# amp.net
KiCad netlist of a schematic drawn in EAGLE
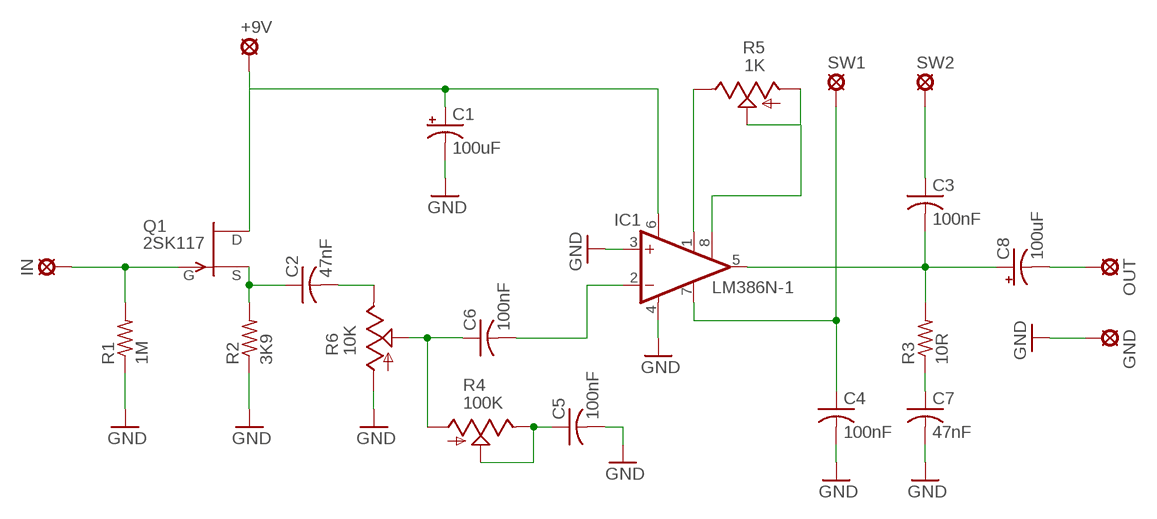
[diagram p0: schematic, sheet 1]

(export (version "E")
  (design (tool "Eeschema 10.0.6"))
  (components
    (comp (ref "+9V")
      (value "MCS10B")
      (footprint "eagle-import:MCS10B")
      (libsource (lib "eagle-import") (part "MCS10B"))
    )
    (comp (ref "C1")
      (value "100uF")
      (footprint "eagle-import:TT2D5")
      (libsource (lib "eagle-import") (part "CPOL-USTT2D5"))
    )
    (comp (ref "C2")
      (value "47nF")
      (footprint "eagle-import:C050-025X075")
      (libsource (lib "eagle-import") (part "C-US050-025X075"))
    )
    (comp (ref "C3")
      (value "100nF")
      (footprint "eagle-import:C050-025X075")
      (libsource (lib "eagle-import") (part "C-US050-025X075"))
    )
    (comp (ref "C4")
      (value "100nF")
      (footprint "eagle-import:C050-025X075")
      (libsource (lib "eagle-import") (part "C-US050-025X075"))
    )
    (comp (ref "C5")
      (value "100nF")
      (footprint "eagle-import:C050-025X075")
      (libsource (lib "eagle-import") (part "C-US050-025X075"))
    )
    (comp (ref "C6")
      (value "100nF")
      (footprint "eagle-import:C050-025X075")
      (libsource (lib "eagle-import") (part "C-US050-025X075"))
    )
    (comp (ref "C7")
      (value "47nF")
      (footprint "eagle-import:C050-025X075")
      (libsource (lib "eagle-import") (part "C-US050-025X075"))
    )
    (comp (ref "C8")
      (value "100uF")
      (footprint "eagle-import:TT2D5")
      (libsource (lib "eagle-import") (part "CPOL-USTT2D5"))
    )
    (comp (ref "GND")
      (value "MCS10B")
      (footprint "eagle-import:MCS10B")
      (libsource (lib "eagle-import") (part "MCS10B"))
    )
    (comp (ref "IC1")
      (value "LM386N-1")
      (footprint "eagle-import:DIL08")
      (libsource (lib "eagle-import") (part "LM386?-N1"))
    )
    (comp (ref "IN")
      (value "MCS10B")
      (footprint "eagle-import:MCS10B")
      (libsource (lib "eagle-import") (part "MCS10B"))
    )
    (comp (ref "OUT")
      (value "MCS10B")
      (footprint "eagle-import:MCS10B")
      (libsource (lib "eagle-import") (part "MCS10B"))
    )
    (comp (ref "Q1")
      (value "2SK117")
      (footprint "eagle-import:TO-92")
      (libsource (lib "eagle-import") (part "2SK117"))
    )
    (comp (ref "R1")
      (value "1M")
      (footprint "eagle-import:0207_7")
      (libsource (lib "eagle-import") (part "R-US_0207/7"))
    )
    (comp (ref "R2")
      (value "3K9")
      (footprint "eagle-import:0207_7")
      (libsource (lib "eagle-import") (part "R-US_0207/7"))
    )
    (comp (ref "R3")
      (value "10R")
      (footprint "eagle-import:0207_7")
      (libsource (lib "eagle-import") (part "R-US_0207/7"))
    )
    (comp (ref "R4")
      (value "100K")
      (footprint "eagle-import:B64Y")
      (libsource (lib "eagle-import") (part "TRIM_US-B64Y"))
    )
    (comp (ref "R5")
      (value "1K")
      (footprint "eagle-import:B64Y")
      (libsource (lib "eagle-import") (part "TRIM_US-B64Y"))
    )
    (comp (ref "R6")
      (value "10K")
      (footprint "eagle-import:B64Y")
      (libsource (lib "eagle-import") (part "TRIM_US-B64Y"))
    )
    (comp (ref "SW1")
      (value "MCS10B")
      (footprint "eagle-import:MCS10B")
      (libsource (lib "eagle-import") (part "MCS10B"))
    )
    (comp (ref "SW2")
      (value "MCS10B")
      (footprint "eagle-import:MCS10B")
      (libsource (lib "eagle-import") (part "MCS10B"))
    )
  )
  (nets
    (net (code "1") (name "GND") (class "Default")
      (node (ref "C1") (pin "-") (pinfunction "-_-") (pintype "passive"))
      (node (ref "C4") (pin "2") (pinfunction "2_2") (pintype "passive"))
      (node (ref "C5") (pin "2") (pinfunction "2_2") (pintype "passive"))
      (node (ref "C7") (pin "2") (pinfunction "2_2") (pintype "passive"))
      (node (ref "GND") (pin "MP") (pinfunction "MP_MP") (pintype "passive"))
      (node (ref "IC1") (pin "3") (pinfunction "+IN_3") (pintype "input"))
      (node (ref "IC1") (pin "4") (pinfunction "GND_4") (pintype "power_in"))
      (node (ref "R1") (pin "1") (pinfunction "1_1") (pintype "passive"))
      (node (ref "R2") (pin "1") (pinfunction "1_1") (pintype "passive"))
      (node (ref "R6") (pin "A") (pinfunction "A_A") (pintype "passive"))
    )
    (net (code "2") (name "Net-(C2-Pad2)") (class "Default")
      (node (ref "C2") (pin "2") (pinfunction "2_2") (pintype "passive"))
      (node (ref "R6") (pin "E") (pinfunction "E_E") (pintype "passive"))
    )
    (net (code "3") (name "Net-(C3-Pad1)") (class "Default")
      (node (ref "C3") (pin "1") (pinfunction "1_1") (pintype "passive"))
      (node (ref "SW2") (pin "MP") (pinfunction "MP_MP") (pintype "passive"))
    )
    (net (code "4") (name "Net-(C5-Pad1)") (class "Default")
      (node (ref "C5") (pin "1") (pinfunction "1_1") (pintype "passive"))
      (node (ref "R4") (pin "E") (pinfunction "E_E") (pintype "passive"))
      (node (ref "R4") (pin "S") (pinfunction "S_S") (pintype "passive"))
    )
    (net (code "5") (name "Net-(C6-Pad1)") (class "Default")
      (node (ref "C6") (pin "1") (pinfunction "1_1") (pintype "passive"))
      (node (ref "R4") (pin "A") (pinfunction "A_A") (pintype "passive"))
      (node (ref "R6") (pin "S") (pinfunction "S_S") (pintype "passive"))
    )
    (net (code "6") (name "Net-(C7-Pad1)") (class "Default")
      (node (ref "C7") (pin "1") (pinfunction "1_1") (pintype "passive"))
      (node (ref "R3") (pin "1") (pinfunction "1_1") (pintype "passive"))
    )
    (net (code "7") (name "Net-(C8-Pad-)") (class "Default")
      (node (ref "C8") (pin "-") (pinfunction "-_-") (pintype "passive"))
      (node (ref "OUT") (pin "MP") (pinfunction "MP_MP") (pintype "passive"))
    )
    (net (code "8") (name "Net-(IC1--IN)") (class "Default")
      (node (ref "C6") (pin "2") (pinfunction "2_2") (pintype "passive"))
      (node (ref "IC1") (pin "2") (pinfunction "-IN_2") (pintype "input"))
    )
    (net (code "9") (name "Net-(IC1-BYPASS)") (class "Default")
      (node (ref "C4") (pin "1") (pinfunction "1_1") (pintype "passive"))
      (node (ref "IC1") (pin "7") (pinfunction "BYPASS_7") (pintype "passive"))
      (node (ref "SW1") (pin "MP") (pinfunction "MP_MP") (pintype "passive"))
    )
    (net (code "10") (name "Net-(IC1-GAIN-Pad1)") (class "Default")
      (node (ref "IC1") (pin "1") (pinfunction "GAIN_1") (pintype "passive"))
      (node (ref "R5") (pin "E") (pinfunction "E_E") (pintype "passive"))
    )
    (net (code "11") (name "Net-(IC1-GAIN-Pad8)") (class "Default")
      (node (ref "IC1") (pin "8") (pinfunction "GAIN_8") (pintype "passive"))
      (node (ref "R5") (pin "A") (pinfunction "A_A") (pintype "passive"))
      (node (ref "R5") (pin "S") (pinfunction "S_S") (pintype "passive"))
    )
    (net (code "12") (name "Net-(IC1-OUT)") (class "Default")
      (node (ref "C3") (pin "2") (pinfunction "2_2") (pintype "passive"))
      (node (ref "C8") (pin "+") (pinfunction "+_+") (pintype "passive"))
      (node (ref "IC1") (pin "5") (pinfunction "OUT_5") (pintype "output"))
      (node (ref "R3") (pin "2") (pinfunction "2_2") (pintype "passive"))
    )
    (net (code "13") (name "Net-(IC1-VS)") (class "Default")
      (node (ref "+9V") (pin "MP") (pinfunction "MP_MP") (pintype "passive"))
      (node (ref "C1") (pin "+") (pinfunction "+_+") (pintype "passive"))
      (node (ref "IC1") (pin "6") (pinfunction "VS_6") (pintype "power_in"))
      (node (ref "Q1") (pin "1") (pinfunction "D_1") (pintype "passive"))
    )
    (net (code "14") (name "Net-(Q1-G)") (class "Default")
      (node (ref "IN") (pin "MP") (pinfunction "MP_MP") (pintype "passive"))
      (node (ref "Q1") (pin "2") (pinfunction "G_2") (pintype "passive"))
      (node (ref "R1") (pin "2") (pinfunction "2_2") (pintype "passive"))
    )
    (net (code "15") (name "Net-(Q1-S)") (class "Default")
      (node (ref "C2") (pin "1") (pinfunction "1_1") (pintype "passive"))
      (node (ref "Q1") (pin "3") (pinfunction "S_3") (pintype "passive"))
      (node (ref "R2") (pin "2") (pinfunction "2_2") (pintype "passive"))
    )
  )
)
